# LCMeter-LCD4BitDirect-18F2550-CMP.net
KiCad netlist of a schematic drawn in EAGLE
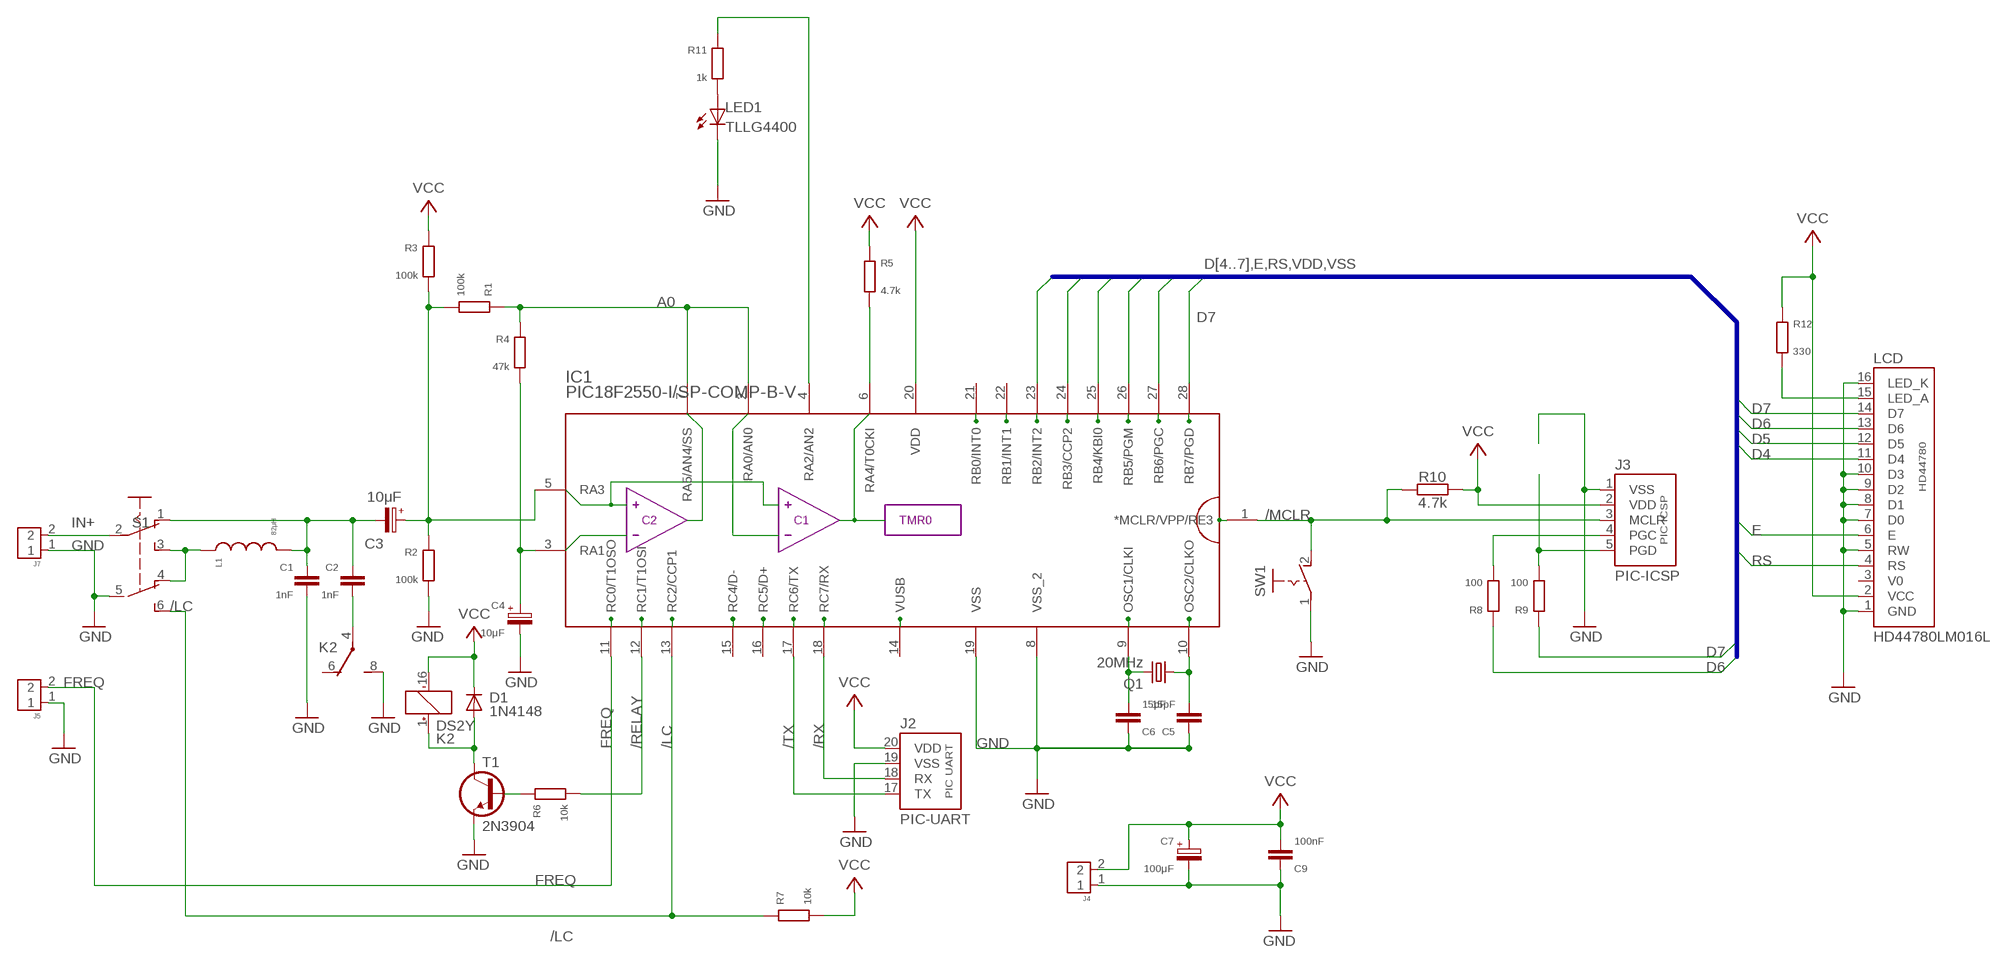
[diagram p0: schematic, sheet 1]

(export (version "E")
  (design (tool "Eeschema 10.0.6"))
  (components
    (comp (ref "C1")
      (value "1nF")
      (footprint "eagle-import:C050-025X060")
      (libsource (lib "eagle-import") (part "C025-025X060"))
    )
    (comp (ref "C2")
      (value "1nF")
      (footprint "eagle-import:C050-025X060")
      (libsource (lib "eagle-import") (part "C025-025X060"))
    )
    (comp (ref "C3")
      (value "10μF")
      (footprint "eagle-import:E2,5-4")
      (libsource (lib "eagle-import") (part "CPOLE2,5-4"))
    )
    (comp (ref "C4")
      (value "10μF")
      (footprint "eagle-import:E2,5-4")
      (libsource (lib "eagle-import") (part "CPOLE2,5-4"))
    )
    (comp (ref "C5")
      (value "15pF")
      (footprint "eagle-import:C025-020X036")
      (libsource (lib "eagle-import") (part "C025-020X036"))
    )
    (comp (ref "C6")
      (value "15pF")
      (footprint "eagle-import:C025-020X036")
      (libsource (lib "eagle-import") (part "C025-020X036"))
    )
    (comp (ref "C7")
      (value "100μF")
      (footprint "eagle-import:E2,5-4")
      (libsource (lib "eagle-import") (part "CPOLE2,5-4"))
    )
    (comp (ref "C9")
      (value "100nF")
      (footprint "eagle-import:C025-020X036_V")
      (libsource (lib "eagle-import") (part "C025-020X036/V"))
    )
    (comp (ref "D1")
      (value "1N4148")
      (footprint "eagle-import:DO34-7")
      (libsource (lib "eagle-import") (part "1N414834-7"))
    )
    (comp (ref "IC1")
      (value "PIC18F2550-I/SP-COMP-B-V")
      (footprint "eagle-import:DIL28-3_V")
      (libsource (lib "eagle-import") (part "PIC18F2550-I/SP-COMP-B-V"))
    )
    (comp (ref "J2")
      (value "PIC-UART")
      (footprint "eagle-import:PIC-UART")
      (libsource (lib "eagle-import") (part "PIC-UART"))
    )
    (comp (ref "J3")
      (value "PIC-ICSP")
      (footprint "eagle-import:PIC-ICSP")
      (libsource (lib "eagle-import") (part "PIC-ICSPICSP"))
    )
    (comp (ref "J4")
      (value "PWR")
      (footprint "eagle-import:CONN-2P")
      (libsource (lib "eagle-import") (part "CONN-2P2P/H"))
    )
    (comp (ref "J5")
      (value "FREQ")
      (footprint "eagle-import:CONN-2P")
      (libsource (lib "eagle-import") (part "CONN-2P2P/H"))
    )
    (comp (ref "J7")
      (value "TEST-LC")
      (footprint "eagle-import:CONN-2P-V")
      (libsource (lib "eagle-import") (part "CONN-2P2P/V"))
    )
    (comp (ref "K2")
      (value "DS2Y")
      (footprint "eagle-import:DS2Y")
      (fields (field (name "MPN") "DS2Y-S-DC5V"))
      (libsource (lib "eagle-import") (part "DS2Y-S-DC5V"))
    )
    (comp (ref "L1")
      (value "82μH")
      (footprint "eagle-import:0204_12")
      (libsource (lib "eagle-import") (part "L0204/12"))
    )
    (comp (ref "LCD")
      (value "HD44780LM016L")
      (footprint "eagle-import:LM016L-HD44780")
      (libsource (lib "eagle-import") (part "HD44780LM016L"))
    )
    (comp (ref "LED1")
      (value "TLLG4400")
      (footprint "eagle-import:LED3MM")
      (fields (field (name "MF") "VISHAY SEMICONDUCTOR"))
      (libsource (lib "eagle-import") (part "TLLG4400"))
    )
    (comp (ref "Q1")
      (value "20MHz")
      (footprint "eagle-import:HC49")
      (libsource (lib "eagle-import") (part "CRYSTALHC49"))
    )
    (comp (ref "R1")
      (value "100k")
      (footprint "eagle-import:0204_10")
      (libsource (lib "eagle-import") (part "R0204/10"))
    )
    (comp (ref "R2")
      (value "100k")
      (footprint "eagle-import:0204_10")
      (libsource (lib "eagle-import") (part "R0204/10"))
    )
    (comp (ref "R3")
      (value "100k")
      (footprint "eagle-import:0204_10")
      (libsource (lib "eagle-import") (part "R0204/10"))
    )
    (comp (ref "R4")
      (value "47k")
      (footprint "eagle-import:0204_10-V")
      (libsource (lib "eagle-import") (part "R0204/10-V"))
    )
    (comp (ref "R5")
      (value "4.7k")
      (footprint "eagle-import:0204_10")
      (libsource (lib "eagle-import") (part "R0204/10"))
    )
    (comp (ref "R6")
      (value "10k")
      (footprint "eagle-import:0204_10-V")
      (libsource (lib "eagle-import") (part "R0204/10-V"))
    )
    (comp (ref "R7")
      (value "10k")
      (footprint "eagle-import:0204_10-V")
      (libsource (lib "eagle-import") (part "R0204/10-V"))
    )
    (comp (ref "R8")
      (value "100")
      (footprint "eagle-import:0204_10-V")
      (libsource (lib "eagle-import") (part "R0204/10-V"))
    )
    (comp (ref "R9")
      (value "100")
      (footprint "eagle-import:0204_10-V")
      (libsource (lib "eagle-import") (part "R0204/10-V"))
    )
    (comp (ref "R10")
      (value "4.7k")
      (footprint "eagle-import:0204_10")
      (libsource (lib "eagle-import") (part "R0204/10"))
    )
    (comp (ref "R11")
      (value "1k")
      (footprint "eagle-import:0204_10-V")
      (libsource (lib "eagle-import") (part "R0204/10-V"))
    )
    (comp (ref "R12")
      (value "330")
      (footprint "eagle-import:0204_12")
      (libsource (lib "eagle-import") (part "R0204/12"))
    )
    (comp (ref "S1")
      (value "SL-SW-2P-2T")
      (footprint "eagle-import:SLSW-2P2T")
      (libsource (lib "eagle-import") (part "SL-SW-2P-2T"))
    )
    (comp (ref "SW1")
      (value "PB-1P-1T")
      (footprint "eagle-import:PB-1P1T")
      (libsource (lib "eagle-import") (part "PB-1P-1T"))
    )
    (comp (ref "T1")
      (value "2N3904")
      (footprint "eagle-import:TO92")
      (libsource (lib "eagle-import") (part "2N3904"))
    )
  )
  (nets
    (net (code "3") (name "/A0") (class "Default")
      (node (ref "IC1") (pin "2") (pinfunction "RA0/AN0_2") (pintype "passive"))
      (node (ref "IC1") (pin "7") (pinfunction "RA5/AN4/SS_7") (pintype "passive"))
      (node (ref "R1") (pin "2") (pinfunction "2_2") (pintype "passive"))
      (node (ref "R4") (pin "2") (pinfunction "2_2") (pintype "passive"))
    )
    (net (code "4") (name "/D4") (class "Default")
      (node (ref "IC1") (pin "25") (pinfunction "RB4/KBI0_25") (pintype "passive"))
      (node (ref "LCD") (pin "11") (pinfunction "D4_11") (pintype "passive"))
    )
    (net (code "5") (name "/D5") (class "Default")
      (node (ref "IC1") (pin "26") (pinfunction "RB5/PGM_26") (pintype "passive"))
      (node (ref "LCD") (pin "12") (pinfunction "D5_12") (pintype "passive"))
    )
    (net (code "6") (name "/D6") (class "Default")
      (node (ref "IC1") (pin "27") (pinfunction "RB6/PGC_27") (pintype "passive"))
      (node (ref "LCD") (pin "13") (pinfunction "D6_13") (pintype "passive"))
      (node (ref "R8") (pin "2") (pinfunction "2_2") (pintype "passive"))
    )
    (net (code "7") (name "/D7") (class "Default")
      (node (ref "IC1") (pin "28") (pinfunction "RB7/PGD_28") (pintype "passive"))
      (node (ref "LCD") (pin "14") (pinfunction "D7_14") (pintype "passive"))
      (node (ref "R9") (pin "2") (pinfunction "2_2") (pintype "passive"))
    )
    (net (code "8") (name "/E") (class "Default")
      (node (ref "IC1") (pin "24") (pinfunction "RB3/CCP2_24") (pintype "passive"))
      (node (ref "LCD") (pin "6") (pinfunction "E_6") (pintype "passive"))
    )
    (net (code "9") (name "/FREQ") (class "Default")
      (node (ref "IC1") (pin "11") (pinfunction "RC0/T1OSO_11") (pintype "passive"))
      (node (ref "J5") (pin "2") (pinfunction "2_2") (pintype "bidirectional"))
    )
    (net (code "10") (name "/IN+") (class "Default")
      (node (ref "J7") (pin "2") (pinfunction "2_2") (pintype "bidirectional"))
      (node (ref "S1") (pin "2") (pinfunction "P_2") (pintype "passive"))
    )
    (net (code "11") (name "/RS") (class "Default")
      (node (ref "IC1") (pin "23") (pinfunction "RB2/INT2_23") (pintype "passive"))
      (node (ref "LCD") (pin "4") (pinfunction "RS_4") (pintype "passive"))
    )
    (net (code "13") (name "/{slash}LC") (class "Default")
      (node (ref "IC1") (pin "13") (pinfunction "RC2/CCP1_13") (pintype "passive"))
      (node (ref "R7") (pin "2") (pinfunction "2_2") (pintype "passive"))
      (node (ref "S1") (pin "6") (pinfunction "S1_6") (pintype "passive"))
    )
    (net (code "14") (name "/{slash}MCLR") (class "Default")
      (node (ref "IC1") (pin "1") (pinfunction "*MCLR/VPP/RE3_1") (pintype "passive"))
      (node (ref "J3") (pin "3") (pinfunction "MCLR_3") (pintype "passive"))
      (node (ref "R10") (pin "2") (pinfunction "2_2") (pintype "passive"))
      (node (ref "SW1") (pin "2") (pinfunction "S_2") (pintype "passive"))
    )
    (net (code "15") (name "/{slash}RELAY") (class "Default")
      (node (ref "IC1") (pin "12") (pinfunction "RC1/T1OSI_12") (pintype "passive"))
      (node (ref "R6") (pin "1") (pinfunction "1_1") (pintype "passive"))
    )
    (net (code "16") (name "/{slash}RX") (class "Default")
      (node (ref "IC1") (pin "18") (pinfunction "RC7/RX_18") (pintype "passive"))
      (node (ref "J2") (pin "18") (pinfunction "RX_18") (pintype "passive"))
    )
    (net (code "17") (name "/{slash}TX") (class "Default")
      (node (ref "IC1") (pin "17") (pinfunction "RC6/TX_17") (pintype "passive"))
      (node (ref "J2") (pin "17") (pinfunction "TX_17") (pintype "passive"))
    )
    (net (code "18") (name "GND") (class "Default")
      (node (ref "C1") (pin "2") (pinfunction "2_2") (pintype "passive"))
      (node (ref "C4") (pin "-") (pinfunction "-_-") (pintype "passive"))
      (node (ref "C5") (pin "1") (pinfunction "1_1") (pintype "passive"))
      (node (ref "C6") (pin "1") (pinfunction "1_1") (pintype "passive"))
      (node (ref "C7") (pin "-") (pinfunction "-_-") (pintype "passive"))
      (node (ref "C9") (pin "1") (pinfunction "1_1") (pintype "passive"))
      (node (ref "IC1") (pin "19") (pinfunction "VSS_19") (pintype "passive"))
      (node (ref "IC1") (pin "8") (pinfunction "VSS_2_8") (pintype "passive"))
      (node (ref "J2") (pin "19") (pinfunction "VSS_19") (pintype "passive"))
      (node (ref "J3") (pin "1") (pinfunction "VSS_1") (pintype "passive"))
      (node (ref "J4") (pin "1") (pinfunction "1_1") (pintype "bidirectional"))
      (node (ref "J5") (pin "1") (pinfunction "1_1") (pintype "bidirectional"))
      (node (ref "J7") (pin "1") (pinfunction "1_1") (pintype "bidirectional"))
      (node (ref "K2") (pin "8") (pinfunction "S_8") (pintype "passive"))
      (node (ref "LCD") (pin "1") (pinfunction "GND_1") (pintype "passive"))
      (node (ref "LCD") (pin "10") (pinfunction "D3_10") (pintype "passive"))
      (node (ref "LCD") (pin "16") (pinfunction "LED_K_16") (pintype "passive"))
      (node (ref "LCD") (pin "5") (pinfunction "RW_5") (pintype "passive"))
      (node (ref "LCD") (pin "7") (pinfunction "D0_7") (pintype "passive"))
      (node (ref "LCD") (pin "8") (pinfunction "D1_8") (pintype "passive"))
      (node (ref "LCD") (pin "9") (pinfunction "D2_9") (pintype "passive"))
      (node (ref "LED1") (pin "K") (pinfunction "C_K") (pintype "passive"))
      (node (ref "R2") (pin "1") (pinfunction "1_1") (pintype "passive"))
      (node (ref "S1") (pin "5") (pinfunction "P1_5") (pintype "passive"))
      (node (ref "SW1") (pin "1") (pinfunction "P_1") (pintype "passive"))
      (node (ref "T1") (pin "1") (pinfunction "E_1") (pintype "passive"))
    )
    (net (code "19") (name "Net-(IC1-OSC1{slash}CLKI)") (class "Default")
      (node (ref "C6") (pin "2") (pinfunction "2_2") (pintype "passive"))
      (node (ref "IC1") (pin "9") (pinfunction "OSC1/CLKI_9") (pintype "passive"))
      (node (ref "Q1") (pin "2") (pinfunction "2_2") (pintype "passive"))
    )
    (net (code "20") (name "Net-(IC1-OSC2{slash}CLKO)") (class "Default")
      (node (ref "C5") (pin "2") (pinfunction "2_2") (pintype "passive"))
      (node (ref "IC1") (pin "10") (pinfunction "OSC2/CLKO_10") (pintype "passive"))
      (node (ref "Q1") (pin "1") (pinfunction "1_1") (pintype "passive"))
    )
    (net (code "21") (name "Net-(IC1-RA1)") (class "Default")
      (node (ref "C4") (pin "+") (pinfunction "+_+") (pintype "passive"))
      (node (ref "IC1") (pin "3") (pinfunction "RA1_3") (pintype "passive"))
      (node (ref "R4") (pin "1") (pinfunction "1_1") (pintype "passive"))
    )
    (net (code "22") (name "Net-(IC1-RA2{slash}AN2)") (class "Default")
      (node (ref "IC1") (pin "4") (pinfunction "RA2/AN2_4") (pintype "passive"))
      (node (ref "R11") (pin "2") (pinfunction "2_2") (pintype "passive"))
    )
    (net (code "23") (name "Net-(IC1-RA3)") (class "Default")
      (node (ref "C3") (pin "+") (pinfunction "+_+") (pintype "passive"))
      (node (ref "IC1") (pin "5") (pinfunction "RA3_5") (pintype "passive"))
      (node (ref "R1") (pin "1") (pinfunction "1_1") (pintype "passive"))
      (node (ref "R2") (pin "2") (pinfunction "2_2") (pintype "passive"))
      (node (ref "R3") (pin "1") (pinfunction "1_1") (pintype "passive"))
    )
    (net (code "24") (name "Net-(IC1-RA4{slash}T0CKI)") (class "Default")
      (node (ref "IC1") (pin "6") (pinfunction "RA4/T0CKI_6") (pintype "passive"))
      (node (ref "R5") (pin "1") (pinfunction "1_1") (pintype "passive"))
    )
    (net (code "25") (name "Net-(J3-PGC)") (class "Default")
      (node (ref "J3") (pin "4") (pinfunction "PGC_4") (pintype "passive"))
      (node (ref "R8") (pin "1") (pinfunction "1_1") (pintype "passive"))
    )
    (net (code "26") (name "Net-(J3-PGD)") (class "Default")
      (node (ref "J3") (pin "5") (pinfunction "PGD_5") (pintype "passive"))
      (node (ref "R9") (pin "1") (pinfunction "1_1") (pintype "passive"))
    )
    (net (code "27") (name "Net-(K2A-+)") (class "Default")
      (node (ref "D1") (pin "A") (pinfunction "A_A") (pintype "passive"))
      (node (ref "K2") (pin "1") (pinfunction "+_1") (pintype "passive"))
      (node (ref "T1") (pin "3") (pinfunction "C_3") (pintype "passive"))
    )
    (net (code "28") (name "Net-(K2B-P)") (class "Default")
      (node (ref "C2") (pin "2") (pinfunction "2_2") (pintype "passive"))
      (node (ref "K2") (pin "4") (pinfunction "P_4") (pintype "passive"))
    )
    (net (code "29") (name "Net-(LCD-LED_A)") (class "Default")
      (node (ref "LCD") (pin "15") (pinfunction "LED_A_15") (pintype "passive"))
      (node (ref "R12") (pin "1") (pinfunction "1_1") (pintype "passive"))
    )
    (net (code "30") (name "Net-(LED1-PadA)") (class "Default")
      (node (ref "LED1") (pin "A") (pinfunction "A_A") (pintype "passive"))
      (node (ref "R11") (pin "1") (pinfunction "1_1") (pintype "passive"))
    )
    (net (code "31") (name "Net-(S1-O)") (class "Default")
      (node (ref "C1") (pin "1") (pinfunction "1_1") (pintype "passive"))
      (node (ref "C2") (pin "1") (pinfunction "1_1") (pintype "passive"))
      (node (ref "C3") (pin "-") (pinfunction "-_-") (pintype "passive"))
      (node (ref "L1") (pin "2") (pinfunction "2_2") (pintype "passive"))
      (node (ref "S1") (pin "1") (pinfunction "O_1") (pintype "passive"))
    )
    (net (code "32") (name "Net-(S1-O1)") (class "Default")
      (node (ref "L1") (pin "1") (pinfunction "1_1") (pintype "passive"))
      (node (ref "S1") (pin "3") (pinfunction "S_3") (pintype "passive"))
      (node (ref "S1") (pin "4") (pinfunction "O1_4") (pintype "passive"))
    )
    (net (code "33") (name "Net-(T1-B)") (class "Default")
      (node (ref "R6") (pin "2") (pinfunction "2_2") (pintype "passive"))
      (node (ref "T1") (pin "2") (pinfunction "B_2") (pintype "passive"))
    )
    (net (code "34") (name "VCC") (class "Default")
      (node (ref "C7") (pin "+") (pinfunction "+_+") (pintype "passive"))
      (node (ref "C9") (pin "2") (pinfunction "2_2") (pintype "passive"))
      (node (ref "D1") (pin "C") (pinfunction "C_C") (pintype "passive"))
      (node (ref "IC1") (pin "20") (pinfunction "VDD_20") (pintype "passive"))
      (node (ref "J2") (pin "20") (pinfunction "VDD_20") (pintype "passive"))
      (node (ref "J3") (pin "2") (pinfunction "VDD_2") (pintype "passive"))
      (node (ref "J4") (pin "2") (pinfunction "2_2") (pintype "bidirectional"))
      (node (ref "K2") (pin "16") (pinfunction "-_16") (pintype "passive"))
      (node (ref "LCD") (pin "2") (pinfunction "VCC_2") (pintype "passive"))
      (node (ref "R10") (pin "1") (pinfunction "1_1") (pintype "passive"))
      (node (ref "R12") (pin "2") (pinfunction "2_2") (pintype "passive"))
      (node (ref "R3") (pin "2") (pinfunction "2_2") (pintype "passive"))
      (node (ref "R5") (pin "2") (pinfunction "2_2") (pintype "passive"))
      (node (ref "R7") (pin "1") (pinfunction "1_1") (pintype "passive"))
    )
    (net (code "35") (name "unconnected-(IC1-RB0{slash}INT0-Pad21)") (class "Default")
      (node (ref "IC1") (pin "21") (pinfunction "RB0/INT0_21") (pintype "passive"))
    )
    (net (code "36") (name "unconnected-(IC1-RB1{slash}INT1-Pad22)") (class "Default")
      (node (ref "IC1") (pin "22") (pinfunction "RB1/INT1_22") (pintype "passive"))
    )
    (net (code "37") (name "unconnected-(IC1-RC4{slash}D--Pad15)") (class "Default")
      (node (ref "IC1") (pin "15") (pinfunction "RC4/D-_15") (pintype "passive"))
    )
    (net (code "38") (name "unconnected-(IC1-RC5{slash}D+-Pad16)") (class "Default")
      (node (ref "IC1") (pin "16") (pinfunction "RC5/D+_16") (pintype "passive"))
    )
    (net (code "39") (name "unconnected-(IC1-VUSB-Pad14)") (class "Default")
      (node (ref "IC1") (pin "14") (pinfunction "VUSB_14") (pintype "passive"))
    )
    (net (code "40") (name "unconnected-(K2B-O-Pad6)") (class "Default")
      (node (ref "K2") (pin "6") (pinfunction "O_6") (pintype "passive"))
    )
    (net (code "41") (name "unconnected-(LCD-V0-Pad3)") (class "Default")
      (node (ref "LCD") (pin "3") (pinfunction "V0_3") (pintype "passive"))
    )
  )
)
